# clock1.net
KiCad netlist of a schematic drawn in Altium Designer
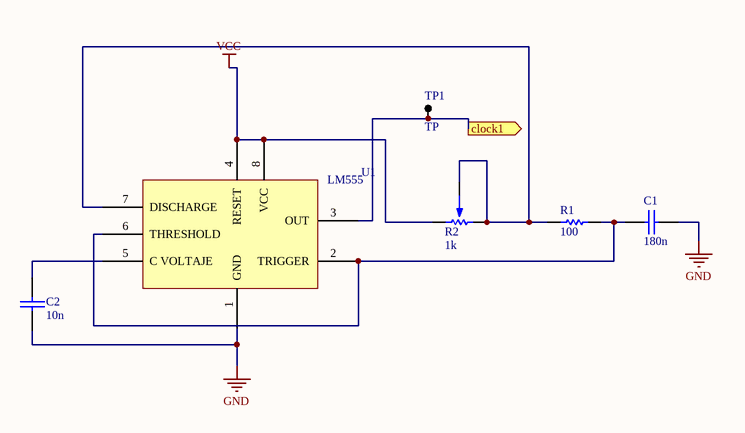
[diagram p0: clock1.SchDoc]

(export (version "E")
  (design (tool "Eeschema 10.0.6"))
  (components
    (comp (ref "C1") (value "180n") (footprint "0805") (libsource (lib "LIBEBAL") (part "CAP")))
    (comp (ref "C2") (value "10n") (footprint "CAP200") (libsource (lib "LIBEBAL") (part "CAP")))
    (comp (ref "R1") (value "100") (footprint "0805") (libsource (lib "LIBEBAL") (part "RES")))
    (comp (ref "R2") (value "1k") (footprint "PRESET H") (libsource (lib "LIBEBAL") (part "PRESET")))
    (comp (ref "TP1") (value "TP") (footprint "TPTH") (libsource (lib "LIBEBAL") (part "TP")))
    (comp (ref "U1")
      (value "LM555")
      (footprint "DIP8")
      (description "Timer")
      (libsource (lib "LIBEBAL") (part "LM555"))
    )
  )
  (nets
    (net (code "1") (name "/clock1") (class "Default")
      (node (ref "TP1") (pin "1") (pinfunction "1_1") (pintype "passive"))
      (node (ref "U1") (pin "3") (pinfunction "OUT_3") (pintype "passive"))
    )
    (net (code "2") (name "GND") (class "Default")
      (node (ref "C1") (pin "2") (pinfunction "2_2") (pintype "passive"))
      (node (ref "C2") (pin "1") (pinfunction "1_1") (pintype "passive"))
      (node (ref "U1") (pin "1") (pinfunction "GND_1") (pintype "passive"))
    )
    (net (code "3") (name "Net-(U1-C_VOLTAJE)") (class "Default")
      (node (ref "C2") (pin "2") (pinfunction "2_2") (pintype "passive"))
      (node (ref "U1") (pin "5") (pinfunction "C_VOLTAJE_5") (pintype "passive"))
    )
    (net (code "4") (name "Net-(U1-DISCHARGE)") (class "Default")
      (node (ref "R1") (pin "1") (pinfunction "1_1") (pintype "passive"))
      (node (ref "R2") (pin "2") (pinfunction "2_2") (pintype "passive"))
      (node (ref "R2") (pin "3") (pinfunction "3_3") (pintype "passive"))
      (node (ref "U1") (pin "7") (pinfunction "DISCHARGE_7") (pintype "passive"))
    )
    (net (code "5") (name "Net-(U1-THRESHOLD)") (class "Default")
      (node (ref "C1") (pin "1") (pinfunction "1_1") (pintype "passive"))
      (node (ref "R1") (pin "2") (pinfunction "2_2") (pintype "passive"))
      (node (ref "U1") (pin "2") (pinfunction "TRIGGER_2") (pintype "passive"))
      (node (ref "U1") (pin "6") (pinfunction "THRESHOLD_6") (pintype "passive"))
    )
    (net (code "6") (name "VCC") (class "Default")
      (node (ref "R2") (pin "1") (pinfunction "1_1") (pintype "passive"))
      (node (ref "U1") (pin "4") (pinfunction "RESET_4") (pintype "passive"))
      (node (ref "U1") (pin "8") (pinfunction "VCC_8") (pintype "passive"))
    )
  )
)
